# POW.net
KiCad netlist of a schematic drawn in Altium Designer
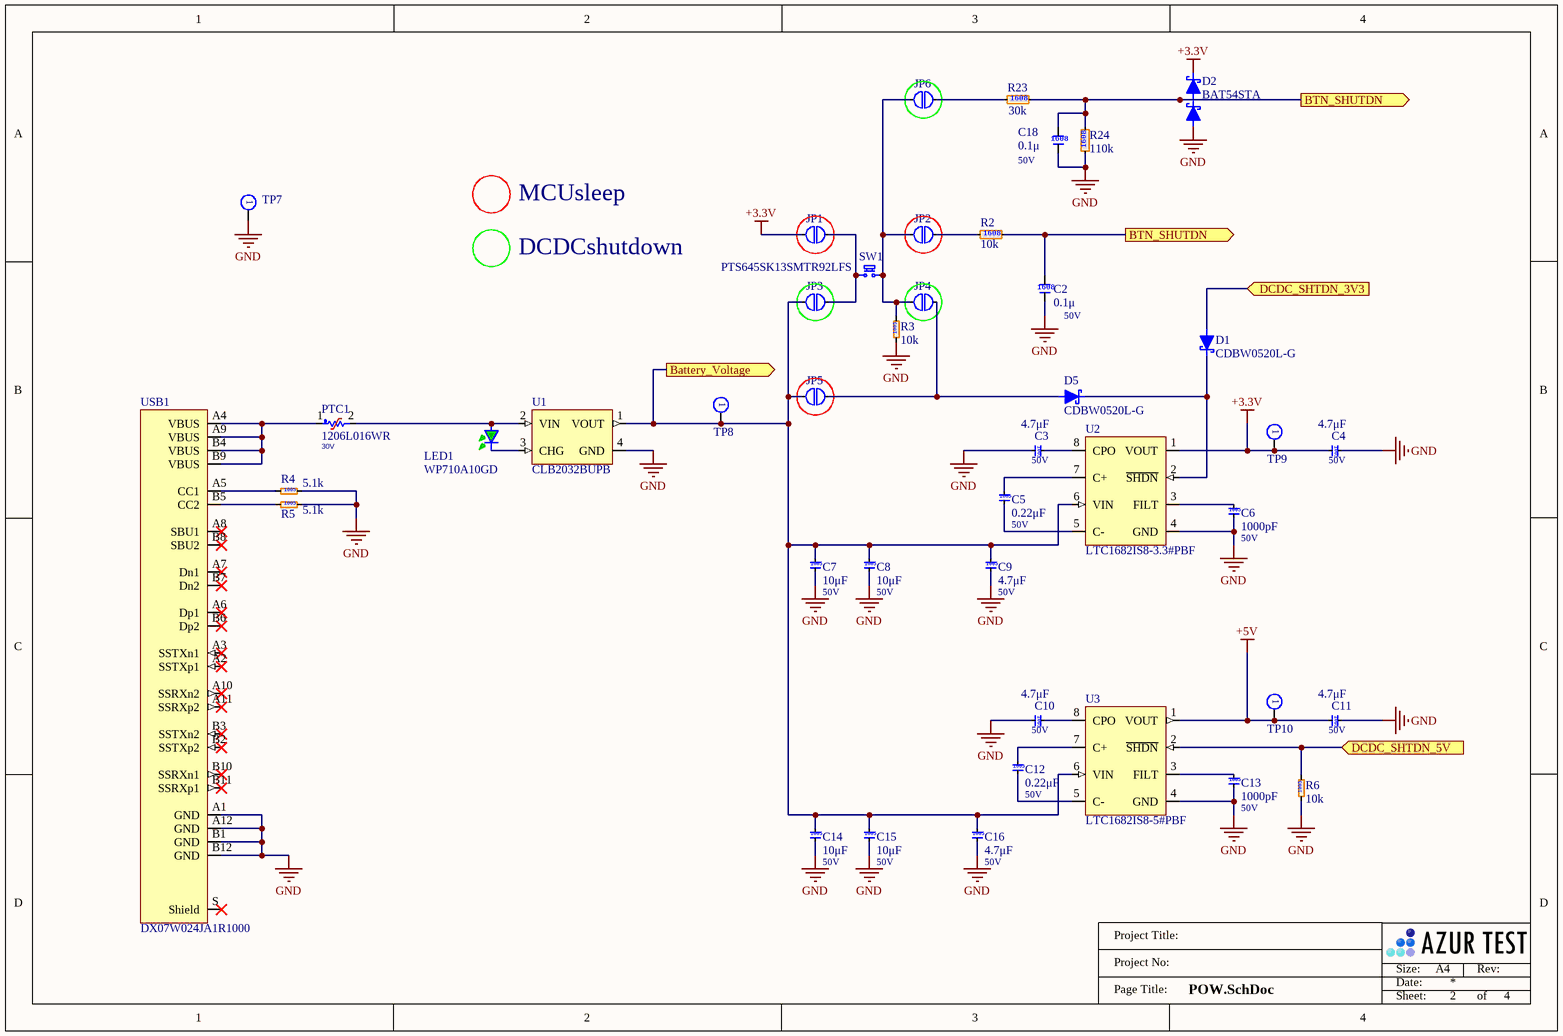
[diagram p0: POW.SchDoc]

(export (version "E")
  (design (tool "Eeschema 10.0.6"))
  (components
    (comp (ref "C2")
      (value "GRM1885C1H101JA01D")
      (footprint "C1608")
      (description "セラコン1608サイズ")
      (fields (field (name "TAG") "0.1μ") (field (name "VOLTAGE") "50V"))
      (libsource (lib "Isoretion wear meater") (part "C1608"))
    )
    (comp (ref "C3")
      (value "GRM155B11H472K")
      (footprint "C1005")
      (description "セラコン1005サイズ")
      (fields (field (name "TAG") "4.7μF") (field (name "VOLTAGE") "50V"))
      (libsource (lib "SSST") (part "C1005"))
    )
    (comp (ref "C4")
      (value "GRM155B11H472K")
      (footprint "C1005")
      (description "セラコン1005サイズ")
      (fields (field (name "TAG") "4.7μF") (field (name "VOLTAGE") "50V"))
      (libsource (lib "SSST") (part "C1005"))
    )
    (comp (ref "C5")
      (value "GRM1552C1H221J")
      (footprint "C1005")
      (description "セラコン1005サイズ")
      (fields (field (name "TAG") "0.22μF") (field (name "VOLTAGE") "50V"))
      (libsource (lib "SSST") (part "C1005"))
    )
    (comp (ref "C6")
      (value "GRM1552C1H102J")
      (footprint "C1005")
      (description "セラコン1005サイズ")
      (fields (field (name "TAG") "1000pF") (field (name "VOLTAGE") "50V"))
      (libsource (lib "SSST") (part "C1005"))
    )
    (comp (ref "C7")
      (value "GRM155F11H103Z")
      (footprint "C1005")
      (description "セラコン1005サイズ")
      (fields (field (name "TAG") "10μF") (field (name "VOLTAGE") "50V"))
      (libsource (lib "SSST") (part "C1005"))
    )
    (comp (ref "C8")
      (value "GRM155F11H103Z")
      (footprint "C1005")
      (description "セラコン1005サイズ")
      (fields (field (name "TAG") "10μF") (field (name "VOLTAGE") "50V"))
      (libsource (lib "SSST") (part "C1005"))
    )
    (comp (ref "C9")
      (value "GRM155B11H472K")
      (footprint "C1005")
      (description "セラコン1005サイズ")
      (fields (field (name "TAG") "4.7μF") (field (name "VOLTAGE") "50V"))
      (libsource (lib "SSST") (part "C1005"))
    )
    (comp (ref "C10")
      (value "GRM155B11H472K")
      (footprint "C1005")
      (description "セラコン1005サイズ")
      (fields (field (name "TAG") "4.7μF") (field (name "VOLTAGE") "50V"))
      (libsource (lib "SSST") (part "C1005"))
    )
    (comp (ref "C11")
      (value "GRM155B11H472K")
      (footprint "C1005")
      (description "セラコン1005サイズ")
      (fields (field (name "TAG") "4.7μF") (field (name "VOLTAGE") "50V"))
      (libsource (lib "SSST") (part "C1005"))
    )
    (comp (ref "C12")
      (value "GRM1552C1H221J")
      (footprint "C1005")
      (description "セラコン1005サイズ")
      (fields (field (name "TAG") "0.22μF") (field (name "VOLTAGE") "50V"))
      (libsource (lib "SSST") (part "C1005"))
    )
    (comp (ref "C13")
      (value "GRM1552C1H102J")
      (footprint "C1005")
      (description "セラコン1005サイズ")
      (fields (field (name "TAG") "1000pF") (field (name "VOLTAGE") "50V"))
      (libsource (lib "SSST") (part "C1005"))
    )
    (comp (ref "C14")
      (value "GRM155F11H103Z")
      (footprint "C1005")
      (description "セラコン1005サイズ")
      (fields (field (name "TAG") "10μF") (field (name "VOLTAGE") "50V"))
      (libsource (lib "SSST") (part "C1005"))
    )
    (comp (ref "C15")
      (value "GRM155F11H103Z")
      (footprint "C1005")
      (description "セラコン1005サイズ")
      (fields (field (name "TAG") "10μF") (field (name "VOLTAGE") "50V"))
      (libsource (lib "SSST") (part "C1005"))
    )
    (comp (ref "C16")
      (value "GRM155B11H472K")
      (footprint "C1005")
      (description "セラコン1005サイズ")
      (fields (field (name "TAG") "4.7μF") (field (name "VOLTAGE") "50V"))
      (libsource (lib "SSST") (part "C1005"))
    )
    (comp (ref "C18")
      (value "GRM1885C1H101JA01D")
      (footprint "C1608")
      (description "セラコン1608サイズ")
      (fields (field (name "TAG") "0.1μ") (field (name "VOLTAGE") "50V"))
      (libsource (lib "Isoretion wear meater") (part "C1608"))
    )
    (comp (ref "D1")
      (value "CDBW0520L-G")
      (footprint "SOD-123")
      (description "Schottky Rectifier")
      (fields (field (name "VOLTAGE") "20V"))
      (libsource (lib "SSST") (part "CDBW0520L-G"))
    )
    (comp (ref "D2")
      (value "BAT54STA")
      (footprint "SOT-23")
      (description "ダブル直列ショットキー")
      (libsource (lib "SSST") (part "BAT54S"))
    )
    (comp (ref "D5")
      (value "CDBW0520L-G")
      (footprint "SOD-123")
      (description "Schottky Rectifier")
      (fields (field (name "VOLTAGE") "20V"))
      (libsource (lib "SSST") (part "CDBW0520L-G"))
    )
    (comp (ref "JP1")
      (value "SMD_JAMPER")
      (footprint "SMD_JAMPER")
      (libsource (lib "SSST") (part "SMD_JAMPER"))
    )
    (comp (ref "JP2")
      (value "SMD_JAMPER")
      (footprint "SMD_JAMPER")
      (libsource (lib "SSST") (part "SMD_JAMPER"))
    )
    (comp (ref "JP3")
      (value "SMD_JAMPER")
      (footprint "SMD_JAMPER")
      (libsource (lib "SSST") (part "SMD_JAMPER"))
    )
    (comp (ref "JP4")
      (value "SMD_JAMPER")
      (footprint "SMD_JAMPER")
      (libsource (lib "SSST") (part "SMD_JAMPER"))
    )
    (comp (ref "JP5")
      (value "SMD_JAMPER")
      (footprint "SMD_JAMPER")
      (libsource (lib "SSST") (part "SMD_JAMPER"))
    )
    (comp (ref "JP6")
      (value "SMD_JAMPER")
      (footprint "SMD_JAMPER")
      (libsource (lib "SSST") (part "SMD_JAMPER"))
    )
    (comp (ref "LED1")
      (value "WP710A10GD")
      (footprint "LED_T1")
      (description "LED T1 GREEN")
      (libsource (lib "SSST") (part "WP710A10GD"))
    )
    (comp (ref "PTC1")
      (value "1206L016WR")
      (footprint "1206L")
      (description "Resettable PTC")
      (fields (field (name "VOLTAGE") "30V"))
      (libsource (lib "SSST") (part "1206L"))
    )
    (comp (ref "R2")
      (value "RG1608P-103-B-T5")
      (footprint "R1608")
      (description "薄膜チップ抵抗1608サイズ")
      (fields (field (name "TAG") "10k"))
      (libsource (lib "SSST") (part "MF1608"))
    )
    (comp (ref "R3")
      (value "RG1005P-103-B-T5")
      (footprint "R1005")
      (description "薄膜チップ抵抗1005サイズ")
      (fields (field (name "TAG") "10k"))
      (libsource (lib "SSST") (part "MF1005"))
    )
    (comp (ref "R4")
      (value "RG1005P-512-B-T5")
      (footprint "R1005")
      (description "薄膜チップ抵抗1005サイズ")
      (fields (field (name "TAG") "5.1k"))
      (libsource (lib "") (part "MF1005_1"))
    )
    (comp (ref "R5")
      (value "RG1005P-512-B-T5")
      (footprint "R1005")
      (description "薄膜チップ抵抗1005サイズ")
      (fields (field (name "TAG") "5.1k"))
      (libsource (lib "") (part "MF1005_1"))
    )
    (comp (ref "R6")
      (value "RG1005P-103-B-T5")
      (footprint "R1005")
      (description "薄膜チップ抵抗1005サイズ")
      (fields (field (name "TAG") "10k"))
      (libsource (lib "SSST") (part "MF1005"))
    )
    (comp (ref "R23")
      (value "RG1608P-303-B-T5")
      (footprint "R1608")
      (description "薄膜チップ抵抗1608サイズ")
      (fields (field (name "TAG") "30k"))
      (libsource (lib "SSST") (part "MF1608"))
    )
    (comp (ref "R24")
      (value "RG1608P-114-B-T5")
      (footprint "R1608")
      (description "薄膜チップ抵抗1608サイズ")
      (fields (field (name "TAG") "110k"))
      (libsource (lib "") (part "MF1608_1"))
    )
    (comp (ref "SW1")
      (value "PTS645SK13SMTR92LFS")
      (footprint "PTS645SK13SMTR92LFS")
      (description "Tactile Switch 6 x 6mm")
      (libsource (lib "SSST") (part "PTS645SK13SMTR92LFS"))
    )
    (comp (ref "TP7")
      (value "TP1mm")
      (footprint "TP1mm")
      (description "Test-Point 1mm")
      (libsource (lib "SSST") (part "TP1mm"))
    )
    (comp (ref "TP8")
      (value "TP1mm")
      (footprint "TP1mm")
      (description "Test-Point 1mm")
      (libsource (lib "SSST") (part "TP1mm"))
    )
    (comp (ref "TP9")
      (value "TP1mm")
      (footprint "TP1mm")
      (description "Test-Point 1mm")
      (libsource (lib "SSST") (part "TP1mm"))
    )
    (comp (ref "TP10")
      (value "TP1mm")
      (footprint "TP1mm")
      (description "Test-Point 1mm")
      (libsource (lib "SSST") (part "TP1mm"))
    )
    (comp (ref "U1")
      (value "CLB2032BUPB")
      (footprint "CLB2032BUPB")
      (description "CLB電池ユニット　ピンタイプ")
      (libsource (lib "SSST") (part "CLB2032BUPB"))
    )
    (comp (ref "U2")
      (value "LTC1682IS8-3.3#PBF")
      (footprint "SOIC8_3.9mm")
      (description "IC REG CHARGE PUMP 3.3V 8SOIC")
      (libsource (lib "SSST") (part "LTC1682IS8-3.3#PBF"))
    )
    (comp (ref "U3")
      (value "LTC1682IS8-5#PBF")
      (footprint "SOIC8_3.9mm")
      (description "IC REG CHARGE PUMP 5V MSOP8")
      (libsource (lib "SSST") (part "LTC1682IS8-5#PBF"))
    )
    (comp (ref "USB1")
      (value "DX07W024JA1R1000")
      (footprint "DX07W024JA1R1000")
      (description "USB3.1 Type-C")
      (libsource (lib "SSST") (part "DX07W024JA1R1000"))
    )
  )
  (nets
    (net (code "1") (name "+3.3V") (class "Default")
      (node (ref "C4") (pin "1") (pinfunction "1_1") (pintype "passive"))
      (node (ref "D2") (pin "2") (pinfunction "K_2") (pintype "passive"))
      (node (ref "JP1") (pin "1") (pinfunction "1_1") (pintype "passive"))
      (node (ref "TP9") (pin "1") (pinfunction "1_1") (pintype "passive"))
      (node (ref "U2") (pin "1") (pinfunction "VOUT_1") (pintype "passive"))
    )
    (net (code "2") (name "+5V") (class "Default")
      (node (ref "C11") (pin "1") (pinfunction "1_1") (pintype "passive"))
      (node (ref "TP10") (pin "1") (pinfunction "1_1") (pintype "passive"))
      (node (ref "U3") (pin "1") (pinfunction "VOUT_1") (pintype "output"))
    )
    (net (code "3") (name "/BTN_SHUTDN") (class "Default")
      (node (ref "C18") (pin "2") (pinfunction "2_2") (pintype "passive"))
      (node (ref "C2") (pin "2") (pinfunction "2_2") (pintype "passive"))
      (node (ref "D2") (pin "3") (pinfunction "C_3") (pintype "passive"))
      (node (ref "R2") (pin "2") (pinfunction "2_2") (pintype "passive"))
      (node (ref "R23") (pin "2") (pinfunction "2_2") (pintype "passive"))
      (node (ref "R24") (pin "2") (pinfunction "2_2") (pintype "passive"))
    )
    (net (code "4") (name "/Battery_Voltage") (class "Default")
      (node (ref "C14") (pin "2") (pinfunction "2_2") (pintype "passive"))
      (node (ref "C15") (pin "2") (pinfunction "2_2") (pintype "passive"))
      (node (ref "C16") (pin "2") (pinfunction "2_2") (pintype "passive"))
      (node (ref "C7") (pin "2") (pinfunction "2_2") (pintype "passive"))
      (node (ref "C8") (pin "2") (pinfunction "2_2") (pintype "passive"))
      (node (ref "C9") (pin "2") (pinfunction "2_2") (pintype "passive"))
      (node (ref "JP3") (pin "1") (pinfunction "1_1") (pintype "passive"))
      (node (ref "JP5") (pin "1") (pinfunction "1_1") (pintype "passive"))
      (node (ref "TP8") (pin "1") (pinfunction "1_1") (pintype "passive"))
      (node (ref "U1") (pin "1") (pinfunction "VOUT_1") (pintype "output"))
      (node (ref "U2") (pin "6") (pinfunction "VIN_6") (pintype "input"))
      (node (ref "U3") (pin "6") (pinfunction "VIN_6") (pintype "input"))
    )
    (net (code "5") (name "/DCDC_SHTDN_3V3") (class "Default")
      (node (ref "D1") (pin "A") (pinfunction "A_A") (pintype "passive"))
    )
    (net (code "6") (name "/DCDC_SHTDN_5V") (class "Default")
      (node (ref "R6") (pin "2") (pinfunction "2_2") (pintype "passive"))
      (node (ref "U3") (pin "2") (pinfunction "~{SHDN}_2") (pintype "input"))
    )
    (net (code "7") (name "GND") (class "Default")
      (node (ref "C10") (pin "1") (pinfunction "1_1") (pintype "passive"))
      (node (ref "C11") (pin "2") (pinfunction "2_2") (pintype "passive"))
      (node (ref "C13") (pin "1") (pinfunction "1_1") (pintype "passive"))
      (node (ref "C14") (pin "1") (pinfunction "1_1") (pintype "passive"))
      (node (ref "C15") (pin "1") (pinfunction "1_1") (pintype "passive"))
      (node (ref "C16") (pin "1") (pinfunction "1_1") (pintype "passive"))
      (node (ref "C18") (pin "1") (pinfunction "1_1") (pintype "passive"))
      (node (ref "C2") (pin "1") (pinfunction "1_1") (pintype "passive"))
      (node (ref "C3") (pin "1") (pinfunction "1_1") (pintype "passive"))
      (node (ref "C4") (pin "2") (pinfunction "2_2") (pintype "passive"))
      (node (ref "C6") (pin "1") (pinfunction "1_1") (pintype "passive"))
      (node (ref "C7") (pin "1") (pinfunction "1_1") (pintype "passive"))
      (node (ref "C8") (pin "1") (pinfunction "1_1") (pintype "passive"))
      (node (ref "C9") (pin "1") (pinfunction "1_1") (pintype "passive"))
      (node (ref "D2") (pin "1") (pinfunction "A_1") (pintype "passive"))
      (node (ref "R24") (pin "1") (pinfunction "1_1") (pintype "passive"))
      (node (ref "R3") (pin "1") (pinfunction "1_1") (pintype "passive"))
      (node (ref "R4") (pin "2") (pinfunction "2_2") (pintype "passive"))
      (node (ref "R5") (pin "2") (pinfunction "2_2") (pintype "passive"))
      (node (ref "R6") (pin "1") (pinfunction "1_1") (pintype "passive"))
      (node (ref "TP7") (pin "1") (pinfunction "1_1") (pintype "passive"))
      (node (ref "U1") (pin "4") (pinfunction "GND_4") (pintype "power_in"))
      (node (ref "U2") (pin "4") (pinfunction "GND_4") (pintype "power_in"))
      (node (ref "U3") (pin "4") (pinfunction "GND_4") (pintype "power_in"))
      (node (ref "USB1") (pin "A1") (pinfunction "GND_A1") (pintype "power_in"))
      (node (ref "USB1") (pin "A12") (pinfunction "GND_A12") (pintype "power_in"))
      (node (ref "USB1") (pin "B1") (pinfunction "GND_B1") (pintype "power_in"))
      (node (ref "USB1") (pin "B12") (pinfunction "GND_B12") (pintype "power_in"))
    )
    (net (code "8") (name "Net-(D5-PadA)") (class "Default")
      (node (ref "D5") (pin "A") (pinfunction "A_A") (pintype "passive"))
      (node (ref "JP4") (pin "2") (pinfunction "2_2") (pintype "passive"))
      (node (ref "JP5") (pin "2") (pinfunction "2_2") (pintype "passive"))
    )
    (net (code "9") (name "Net-(JP1-Pad2)") (class "Default")
      (node (ref "JP1") (pin "2") (pinfunction "2_2") (pintype "passive"))
      (node (ref "JP3") (pin "2") (pinfunction "2_2") (pintype "passive"))
      (node (ref "SW1") (pin "1") (pinfunction "1_1") (pintype "passive"))
      (node (ref "SW1") (pin "2") (pinfunction "2_2") (pintype "passive"))
    )
    (net (code "10") (name "Net-(JP2-Pad1)") (class "Default")
      (node (ref "JP2") (pin "1") (pinfunction "1_1") (pintype "passive"))
      (node (ref "JP4") (pin "1") (pinfunction "1_1") (pintype "passive"))
      (node (ref "JP6") (pin "1") (pinfunction "1_1") (pintype "passive"))
      (node (ref "R3") (pin "2") (pinfunction "2_2") (pintype "passive"))
      (node (ref "SW1") (pin "3") (pinfunction "3_3") (pintype "passive"))
      (node (ref "SW1") (pin "4") (pinfunction "4_4") (pintype "passive"))
    )
    (net (code "11") (name "Net-(JP2-Pad2)") (class "Default")
      (node (ref "JP2") (pin "2") (pinfunction "2_2") (pintype "passive"))
      (node (ref "R2") (pin "1") (pinfunction "1_1") (pintype "passive"))
    )
    (net (code "12") (name "Net-(JP6-Pad2)") (class "Default")
      (node (ref "JP6") (pin "2") (pinfunction "2_2") (pintype "passive"))
      (node (ref "R23") (pin "1") (pinfunction "1_1") (pintype "passive"))
    )
    (net (code "13") (name "Net-(PTC1-Pad1)") (class "Default")
      (node (ref "PTC1") (pin "1") (pinfunction "1_1") (pintype "passive"))
      (node (ref "USB1") (pin "A4") (pinfunction "VBUS_A4") (pintype "passive"))
      (node (ref "USB1") (pin "A9") (pinfunction "VBUS_A9") (pintype "passive"))
      (node (ref "USB1") (pin "B4") (pinfunction "VBUS_B4") (pintype "passive"))
      (node (ref "USB1") (pin "B9") (pinfunction "VBUS_B9") (pintype "passive"))
    )
    (net (code "14") (name "Net-(U1-CHG)") (class "Default")
      (node (ref "LED1") (pin "K") (pinfunction "K_K") (pintype "passive"))
      (node (ref "U1") (pin "3") (pinfunction "CHG_3") (pintype "input"))
    )
    (net (code "15") (name "Net-(U1-VIN)") (class "Default")
      (node (ref "LED1") (pin "A") (pinfunction "A_A") (pintype "passive"))
      (node (ref "PTC1") (pin "2") (pinfunction "2_2") (pintype "passive"))
      (node (ref "U1") (pin "2") (pinfunction "VIN_2") (pintype "input"))
    )
    (net (code "16") (name "Net-(U2-C+)") (class "Default")
      (node (ref "C5") (pin "2") (pinfunction "2_2") (pintype "passive"))
      (node (ref "U2") (pin "7") (pinfunction "C+_7") (pintype "passive"))
    )
    (net (code "17") (name "Net-(U2-C-)") (class "Default")
      (node (ref "C5") (pin "1") (pinfunction "1_1") (pintype "passive"))
      (node (ref "U2") (pin "5") (pinfunction "C-_5") (pintype "passive"))
    )
    (net (code "18") (name "Net-(U2-CPO)") (class "Default")
      (node (ref "C3") (pin "2") (pinfunction "2_2") (pintype "passive"))
      (node (ref "U2") (pin "8") (pinfunction "CPO_8") (pintype "passive"))
    )
    (net (code "19") (name "Net-(U2-FILT)") (class "Default")
      (node (ref "C6") (pin "2") (pinfunction "2_2") (pintype "passive"))
      (node (ref "U2") (pin "3") (pinfunction "FILT_3") (pintype "passive"))
    )
    (net (code "20") (name "Net-(U2-~{SHDN})") (class "Default")
      (node (ref "D1") (pin "K") (pinfunction "K_K") (pintype "passive"))
      (node (ref "D5") (pin "K") (pinfunction "K_K") (pintype "passive"))
      (node (ref "U2") (pin "2") (pinfunction "~{SHDN}_2") (pintype "input"))
    )
    (net (code "21") (name "Net-(U3-C+)") (class "Default")
      (node (ref "C12") (pin "2") (pinfunction "2_2") (pintype "passive"))
      (node (ref "U3") (pin "7") (pinfunction "C+_7") (pintype "passive"))
    )
    (net (code "22") (name "Net-(U3-C-)") (class "Default")
      (node (ref "C12") (pin "1") (pinfunction "1_1") (pintype "passive"))
      (node (ref "U3") (pin "5") (pinfunction "C-_5") (pintype "passive"))
    )
    (net (code "23") (name "Net-(U3-CPO)") (class "Default")
      (node (ref "C10") (pin "2") (pinfunction "2_2") (pintype "passive"))
      (node (ref "U3") (pin "8") (pinfunction "CPO_8") (pintype "passive"))
    )
    (net (code "24") (name "Net-(U3-FILT)") (class "Default")
      (node (ref "C13") (pin "2") (pinfunction "2_2") (pintype "passive"))
      (node (ref "U3") (pin "3") (pinfunction "FILT_3") (pintype "passive"))
    )
    (net (code "25") (name "Net-(USB1-CC1)") (class "Default")
      (node (ref "R4") (pin "1") (pinfunction "1_1") (pintype "passive"))
      (node (ref "USB1") (pin "A5") (pinfunction "CC1_A5") (pintype "passive"))
    )
    (net (code "26") (name "Net-(USB1-CC2)") (class "Default")
      (node (ref "R5") (pin "1") (pinfunction "1_1") (pintype "passive"))
      (node (ref "USB1") (pin "B5") (pinfunction "CC2_B5") (pintype "passive"))
    )
    (net (code "27") (name "unconnected-(USB1-Dn1-PadA7)") (class "Default")
      (node (ref "USB1") (pin "A7") (pinfunction "Dn1_A7") (pintype "bidirectional+no_connect"))
    )
    (net (code "28") (name "unconnected-(USB1-Dn2-PadB7)") (class "Default")
      (node (ref "USB1") (pin "B7") (pinfunction "Dn2_B7") (pintype "bidirectional+no_connect"))
    )
    (net (code "29") (name "unconnected-(USB1-Dp1-PadA6)") (class "Default")
      (node (ref "USB1") (pin "A6") (pinfunction "Dp1_A6") (pintype "bidirectional+no_connect"))
    )
    (net (code "30") (name "unconnected-(USB1-Dp2-PadB6)") (class "Default")
      (node (ref "USB1") (pin "B6") (pinfunction "Dp2_B6") (pintype "bidirectional+no_connect"))
    )
    (net (code "31") (name "unconnected-(USB1-SBU1-PadA8)") (class "Default")
      (node (ref "USB1") (pin "A8") (pinfunction "SBU1_A8") (pintype "passive+no_connect"))
    )
    (net (code "32") (name "unconnected-(USB1-SBU2-PadB8)") (class "Default")
      (node (ref "USB1") (pin "B8") (pinfunction "SBU2_B8") (pintype "passive+no_connect"))
    )
    (net (code "33") (name "unconnected-(USB1-SSRXn1-PadB10)") (class "Default")
      (node (ref "USB1") (pin "B10") (pinfunction "SSRXn1_B10") (pintype "output+no_connect"))
    )
    (net (code "34") (name "unconnected-(USB1-SSRXn2-PadA10)") (class "Default")
      (node (ref "USB1") (pin "A10") (pinfunction "SSRXn2_A10") (pintype "output+no_connect"))
    )
    (net (code "35") (name "unconnected-(USB1-SSRXp1-PadB11)") (class "Default")
      (node (ref "USB1") (pin "B11") (pinfunction "SSRXp1_B11") (pintype "output+no_connect"))
    )
    (net (code "36") (name "unconnected-(USB1-SSRXp2-PadA11)") (class "Default")
      (node (ref "USB1") (pin "A11") (pinfunction "SSRXp2_A11") (pintype "output+no_connect"))
    )
    (net (code "37") (name "unconnected-(USB1-SSTXn1-PadA3)") (class "Default")
      (node (ref "USB1") (pin "A3") (pinfunction "SSTXn1_A3") (pintype "input+no_connect"))
    )
    (net (code "38") (name "unconnected-(USB1-SSTXn2-PadB3)") (class "Default")
      (node (ref "USB1") (pin "B3") (pinfunction "SSTXn2_B3") (pintype "input+no_connect"))
    )
    (net (code "39") (name "unconnected-(USB1-SSTXp1-PadA2)") (class "Default")
      (node (ref "USB1") (pin "A2") (pinfunction "SSTXp1_A2") (pintype "input+no_connect"))
    )
    (net (code "40") (name "unconnected-(USB1-SSTXp2-PadB2)") (class "Default")
      (node (ref "USB1") (pin "B2") (pinfunction "SSTXp2_B2") (pintype "input+no_connect"))
    )
    (net (code "41") (name "unconnected-(USB1-Shield-PadS)") (class "Default")
      (node (ref "USB1") (pin "S") (pinfunction "Shield_S") (pintype "passive+no_connect"))
    )
  )
)
